# POWR0005.net
KiCad netlist of a schematic drawn in Altium Designer
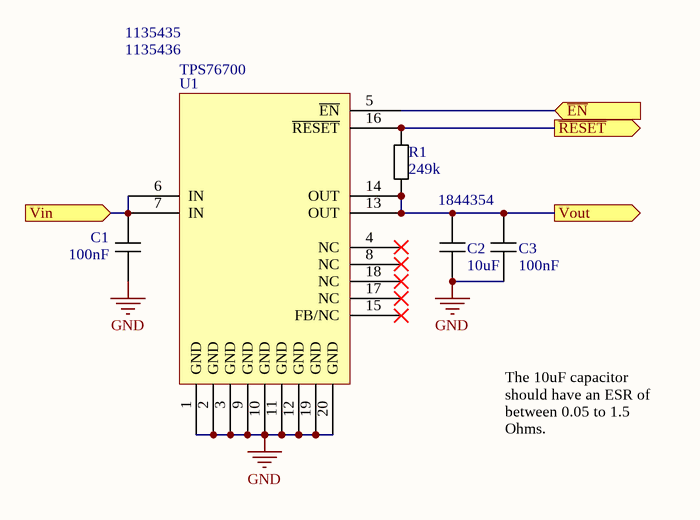
[diagram p0: POWR0005.SchDoc]

(export (version "E")
  (design (tool "Eeschema 10.0.6"))
  (components
    (comp (ref "C1")
      (value "100nF")
      (footprint "0805 Cap")
      (description "0805 MLCC - X7R, 10%")
      (fields (field (name "Comment") "0805 Cap"))
      (libsource (lib "Schlib1") (part "0805 MLCC - X7R, 10%"))
    )
    (comp (ref "C2")
      (value "10uF")
      (footprint "1210 Cap")
      (description "1210 MLCC - X7R, 10%")
      (fields (field (name "SUPPLIER PART NUMBER 1") "1844354") (field (name "Comment") "1210 Cap"))
      (libsource (lib "Schlib1") (part "1210 MLCC - X7R, 10%"))
    )
    (comp (ref "C3")
      (value "100nF")
      (footprint "0805 Cap")
      (description "0805 MLCC - X7R, 10%")
      (fields (field (name "Comment") "0805 Cap"))
      (libsource (lib "Schlib1") (part "0805 MLCC - X7R, 10%"))
    )
    (comp (ref "R1")
      (value "249k")
      (footprint "0805 Resistor")
      (description "0805 Thick Film Resistor 1%")
      (fields (field (name "Comment") "0805 Resistor"))
      (libsource (lib "Schlib1") (part "0805 Thick Film Resistor 1%"))
    )
    (comp (ref "U1")
      (value "TPS76700")
      (footprint "SOP-20 TPS76700")
      (description "LDO Regulator - ER")
      (fields
        (field (name "SUPPLIER PART NUMBER 1") "1135436")
        (field (name "SUPPLIER PART NUMBER 2") "1135435")
      )
      (libsource (lib "Schlib1") (part "TPS76700"))
    )
  )
  (nets
    (net (code "1") (name "/Vin") (class "Default")
      (node (ref "C1") (pin "2") (pinfunction "2_2") (pintype "passive"))
      (node (ref "U1") (pin "6") (pinfunction "IN_6") (pintype "passive"))
      (node (ref "U1") (pin "7") (pinfunction "IN_7") (pintype "passive"))
    )
    (net (code "2") (name "/Vout") (class "Default")
      (node (ref "C2") (pin "2") (pinfunction "2_2") (pintype "passive"))
      (node (ref "C3") (pin "2") (pinfunction "2_2") (pintype "passive"))
      (node (ref "R1") (pin "1") (pinfunction "1_1") (pintype "passive"))
      (node (ref "U1") (pin "13") (pinfunction "OUT_13") (pintype "passive"))
      (node (ref "U1") (pin "14") (pinfunction "OUT_14") (pintype "passive"))
    )
    (net (code "3") (name "/~{EN}") (class "Default")
      (node (ref "U1") (pin "5") (pinfunction "~{EN}_5") (pintype "passive"))
    )
    (net (code "4") (name "/~{RESET}") (class "Default")
      (node (ref "R1") (pin "2") (pinfunction "2_2") (pintype "passive"))
      (node (ref "U1") (pin "16") (pinfunction "~{RESET}_16") (pintype "passive"))
    )
    (net (code "5") (name "GND") (class "Default")
      (node (ref "C1") (pin "1") (pinfunction "1_1") (pintype "passive"))
      (node (ref "C2") (pin "1") (pinfunction "1_1") (pintype "passive"))
      (node (ref "C3") (pin "1") (pinfunction "1_1") (pintype "passive"))
      (node (ref "U1") (pin "1") (pinfunction "GND_1") (pintype "passive"))
      (node (ref "U1") (pin "10") (pinfunction "GND_10") (pintype "passive"))
      (node (ref "U1") (pin "11") (pinfunction "GND_11") (pintype "passive"))
      (node (ref "U1") (pin "12") (pinfunction "GND_12") (pintype "passive"))
      (node (ref "U1") (pin "19") (pinfunction "GND_19") (pintype "passive"))
      (node (ref "U1") (pin "2") (pinfunction "GND_2") (pintype "passive"))
      (node (ref "U1") (pin "20") (pinfunction "GND_20") (pintype "passive"))
      (node (ref "U1") (pin "3") (pinfunction "GND_3") (pintype "passive"))
      (node (ref "U1") (pin "9") (pinfunction "GND_9") (pintype "passive"))
    )
    (net (code "6") (name "unconnected-(U1-FB{slash}NC-Pad15)") (class "Default")
      (node (ref "U1") (pin "15") (pinfunction "FB/NC_15") (pintype "passive+no_connect"))
    )
    (net (code "7") (name "unconnected-(U1-NC-Pad4)") (class "Default")
      (node (ref "U1") (pin "4") (pinfunction "NC_4") (pintype "passive+no_connect"))
    )
    (net (code "8") (name "unconnected-(U1-NC-Pad8)") (class "Default")
      (node (ref "U1") (pin "8") (pinfunction "NC_8") (pintype "passive+no_connect"))
    )
    (net (code "9") (name "unconnected-(U1-NC-Pad17)") (class "Default")
      (node (ref "U1") (pin "17") (pinfunction "NC_17") (pintype "passive+no_connect"))
    )
    (net (code "10") (name "unconnected-(U1-NC-Pad18)") (class "Default")
      (node (ref "U1") (pin "18") (pinfunction "NC_18") (pintype "passive+no_connect"))
    )
  )
)
